# gs_box_board.net
KiCad netlist of a schematic drawn in EAGLE
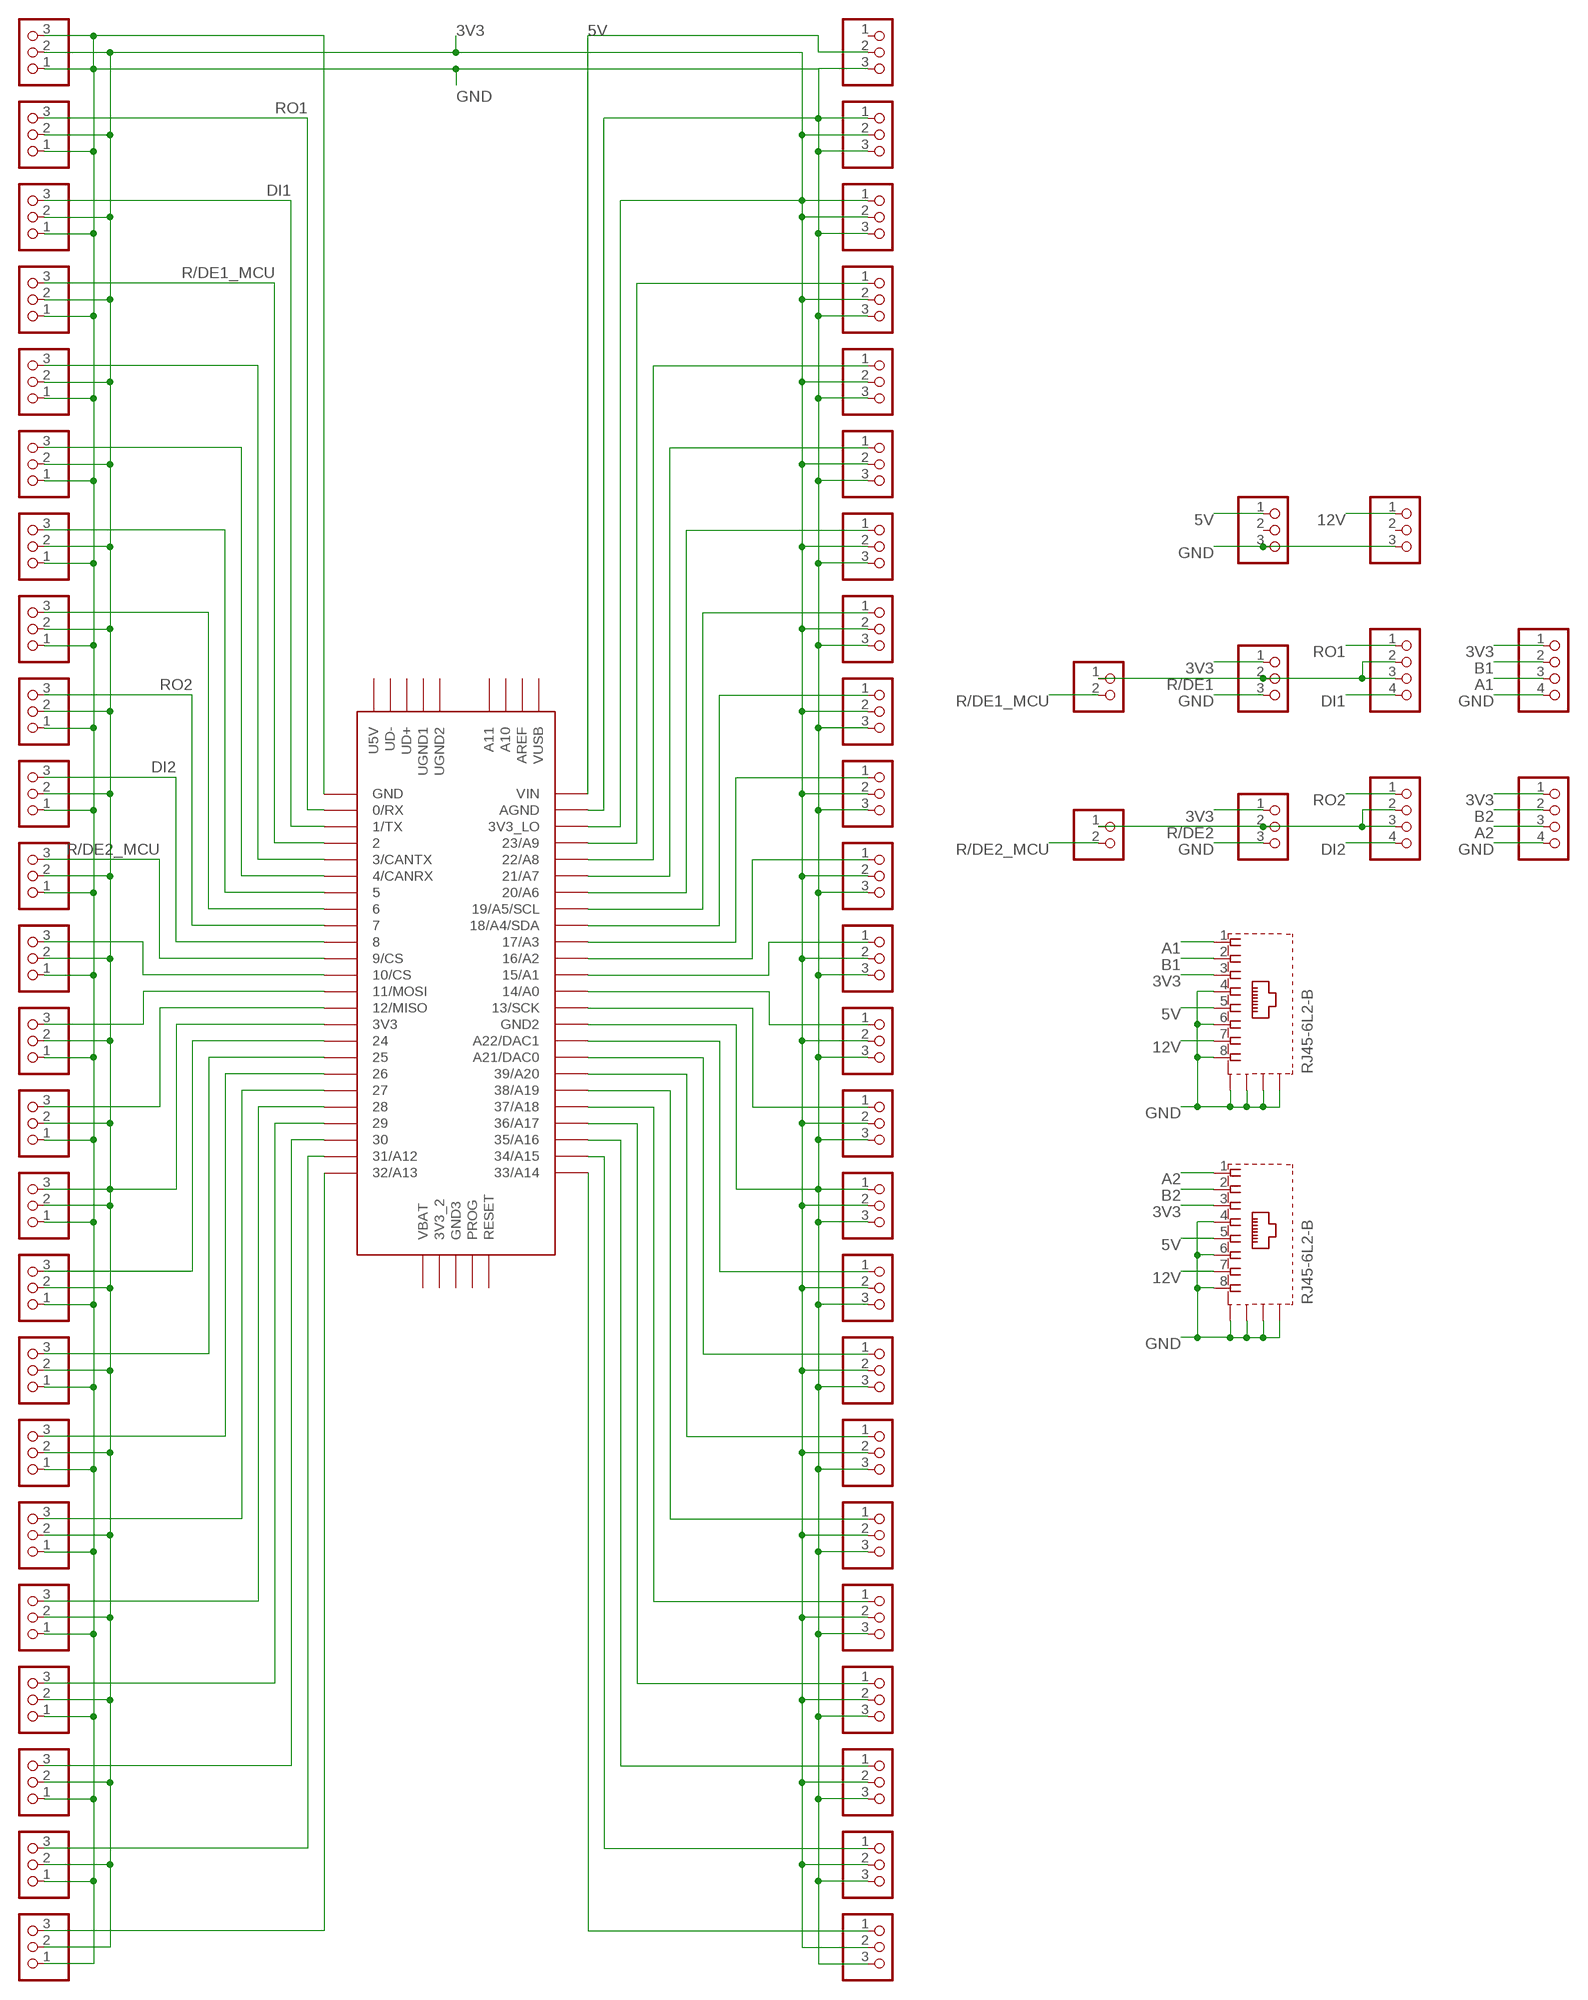
[diagram p0: schematic, sheet 1]

(export (version "E")
  (design (tool "Eeschema 10.0.6"))
  (components
    (comp (ref "JP1")
      (value "PINHD-1X3")
      (footprint "eagle-import:1X03")
      (libsource (lib "eagle-import") (part "PINHD-1X3"))
    )
    (comp (ref "JP2")
      (value "PINHD-1X3")
      (footprint "eagle-import:1X03")
      (libsource (lib "eagle-import") (part "PINHD-1X3"))
    )
    (comp (ref "JP3")
      (value "PINHD-1X3")
      (footprint "eagle-import:1X03")
      (libsource (lib "eagle-import") (part "PINHD-1X3"))
    )
    (comp (ref "JP4")
      (value "PINHD-1X3")
      (footprint "eagle-import:1X03")
      (libsource (lib "eagle-import") (part "PINHD-1X3"))
    )
    (comp (ref "JP5")
      (value "PINHD-1X3")
      (footprint "eagle-import:1X03")
      (libsource (lib "eagle-import") (part "PINHD-1X3"))
    )
    (comp (ref "JP6")
      (value "PINHD-1X3")
      (footprint "eagle-import:1X03")
      (libsource (lib "eagle-import") (part "PINHD-1X3"))
    )
    (comp (ref "JP7")
      (value "PINHD-1X3")
      (footprint "eagle-import:1X03")
      (libsource (lib "eagle-import") (part "PINHD-1X3"))
    )
    (comp (ref "JP8")
      (value "PINHD-1X3")
      (footprint "eagle-import:1X03")
      (libsource (lib "eagle-import") (part "PINHD-1X3"))
    )
    (comp (ref "JP9")
      (value "PINHD-1X3")
      (footprint "eagle-import:1X03")
      (libsource (lib "eagle-import") (part "PINHD-1X3"))
    )
    (comp (ref "JP10")
      (value "PINHD-1X3")
      (footprint "eagle-import:1X03")
      (libsource (lib "eagle-import") (part "PINHD-1X3"))
    )
    (comp (ref "JP11")
      (value "PINHD-1X3")
      (footprint "eagle-import:1X03")
      (libsource (lib "eagle-import") (part "PINHD-1X3"))
    )
    (comp (ref "JP12")
      (value "PINHD-1X3")
      (footprint "eagle-import:1X03")
      (libsource (lib "eagle-import") (part "PINHD-1X3"))
    )
    (comp (ref "JP13")
      (value "PINHD-1X3")
      (footprint "eagle-import:1X03")
      (libsource (lib "eagle-import") (part "PINHD-1X3"))
    )
    (comp (ref "JP14")
      (value "PINHD-1X3")
      (footprint "eagle-import:1X03")
      (libsource (lib "eagle-import") (part "PINHD-1X3"))
    )
    (comp (ref "JP15")
      (value "PINHD-1X3")
      (footprint "eagle-import:1X03")
      (libsource (lib "eagle-import") (part "PINHD-1X3"))
    )
    (comp (ref "JP16")
      (value "PINHD-1X3")
      (footprint "eagle-import:1X03")
      (libsource (lib "eagle-import") (part "PINHD-1X3"))
    )
    (comp (ref "JP17")
      (value "PINHD-1X3")
      (footprint "eagle-import:1X03")
      (libsource (lib "eagle-import") (part "PINHD-1X3"))
    )
    (comp (ref "JP18")
      (value "PINHD-1X3")
      (footprint "eagle-import:1X03")
      (libsource (lib "eagle-import") (part "PINHD-1X3"))
    )
    (comp (ref "JP19")
      (value "PINHD-1X3")
      (footprint "eagle-import:1X03")
      (libsource (lib "eagle-import") (part "PINHD-1X3"))
    )
    (comp (ref "JP20")
      (value "PINHD-1X3")
      (footprint "eagle-import:1X03")
      (libsource (lib "eagle-import") (part "PINHD-1X3"))
    )
    (comp (ref "JP21")
      (value "PINHD-1X3")
      (footprint "eagle-import:1X03")
      (libsource (lib "eagle-import") (part "PINHD-1X3"))
    )
    (comp (ref "JP22")
      (value "PINHD-1X3")
      (footprint "eagle-import:1X03")
      (libsource (lib "eagle-import") (part "PINHD-1X3"))
    )
    (comp (ref "JP23")
      (value "PINHD-1X3")
      (footprint "eagle-import:1X03")
      (libsource (lib "eagle-import") (part "PINHD-1X3"))
    )
    (comp (ref "JP24")
      (value "PINHD-1X3")
      (footprint "eagle-import:1X03")
      (libsource (lib "eagle-import") (part "PINHD-1X3"))
    )
    (comp (ref "JP25")
      (value "PINHD-1X3")
      (footprint "eagle-import:1X03")
      (libsource (lib "eagle-import") (part "PINHD-1X3"))
    )
    (comp (ref "JP26")
      (value "PINHD-1X3")
      (footprint "eagle-import:1X03")
      (libsource (lib "eagle-import") (part "PINHD-1X3"))
    )
    (comp (ref "JP27")
      (value "PINHD-1X3")
      (footprint "eagle-import:1X03")
      (libsource (lib "eagle-import") (part "PINHD-1X3"))
    )
    (comp (ref "JP28")
      (value "PINHD-1X3")
      (footprint "eagle-import:1X03")
      (libsource (lib "eagle-import") (part "PINHD-1X3"))
    )
    (comp (ref "JP29")
      (value "PINHD-1X3")
      (footprint "eagle-import:1X03")
      (libsource (lib "eagle-import") (part "PINHD-1X3"))
    )
    (comp (ref "JP30")
      (value "PINHD-1X3")
      (footprint "eagle-import:1X03")
      (libsource (lib "eagle-import") (part "PINHD-1X3"))
    )
    (comp (ref "JP31")
      (value "PINHD-1X3")
      (footprint "eagle-import:1X03")
      (libsource (lib "eagle-import") (part "PINHD-1X3"))
    )
    (comp (ref "JP32")
      (value "PINHD-1X3")
      (footprint "eagle-import:1X03")
      (libsource (lib "eagle-import") (part "PINHD-1X3"))
    )
    (comp (ref "JP33")
      (value "PINHD-1X3")
      (footprint "eagle-import:1X03")
      (libsource (lib "eagle-import") (part "PINHD-1X3"))
    )
    (comp (ref "JP34")
      (value "PINHD-1X3")
      (footprint "eagle-import:1X03")
      (libsource (lib "eagle-import") (part "PINHD-1X3"))
    )
    (comp (ref "JP35")
      (value "PINHD-1X3")
      (footprint "eagle-import:1X03")
      (libsource (lib "eagle-import") (part "PINHD-1X3"))
    )
    (comp (ref "JP36")
      (value "PINHD-1X3")
      (footprint "eagle-import:1X03")
      (libsource (lib "eagle-import") (part "PINHD-1X3"))
    )
    (comp (ref "JP37")
      (value "PINHD-1X3")
      (footprint "eagle-import:1X03")
      (libsource (lib "eagle-import") (part "PINHD-1X3"))
    )
    (comp (ref "JP38")
      (value "PINHD-1X3")
      (footprint "eagle-import:1X03")
      (libsource (lib "eagle-import") (part "PINHD-1X3"))
    )
    (comp (ref "JP39")
      (value "PINHD-1X3")
      (footprint "eagle-import:1X03")
      (libsource (lib "eagle-import") (part "PINHD-1X3"))
    )
    (comp (ref "JP40")
      (value "PINHD-1X3")
      (footprint "eagle-import:1X03")
      (libsource (lib "eagle-import") (part "PINHD-1X3"))
    )
    (comp (ref "JP41")
      (value "PINHD-1X3")
      (footprint "eagle-import:1X03")
      (libsource (lib "eagle-import") (part "PINHD-1X3"))
    )
    (comp (ref "JP42")
      (value "PINHD-1X3")
      (footprint "eagle-import:1X03")
      (libsource (lib "eagle-import") (part "PINHD-1X3"))
    )
    (comp (ref "JP43")
      (value "PINHD-1X3")
      (footprint "eagle-import:1X03")
      (libsource (lib "eagle-import") (part "PINHD-1X3"))
    )
    (comp (ref "JP44")
      (value "PINHD-1X3")
      (footprint "eagle-import:1X03")
      (libsource (lib "eagle-import") (part "PINHD-1X3"))
    )
    (comp (ref "JP45")
      (value "PINHD-1X3")
      (footprint "eagle-import:1X03")
      (libsource (lib "eagle-import") (part "PINHD-1X3"))
    )
    (comp (ref "JP46")
      (value "PINHD-1X3")
      (footprint "eagle-import:1X03")
      (libsource (lib "eagle-import") (part "PINHD-1X3"))
    )
    (comp (ref "JP47")
      (value "PINHD-1X3")
      (footprint "eagle-import:1X03")
      (libsource (lib "eagle-import") (part "PINHD-1X3"))
    )
    (comp (ref "JP48")
      (value "PINHD-1X3")
      (footprint "eagle-import:1X03")
      (libsource (lib "eagle-import") (part "PINHD-1X3"))
    )
    (comp (ref "JP49")
      (value "PINHD-1X4")
      (footprint "eagle-import:1X04")
      (libsource (lib "eagle-import") (part "PINHD-1X4"))
    )
    (comp (ref "JP50")
      (value "PINHD-1X4")
      (footprint "eagle-import:1X04")
      (libsource (lib "eagle-import") (part "PINHD-1X4"))
    )
    (comp (ref "JP51")
      (value "PINHD-1X4")
      (footprint "eagle-import:1X04")
      (libsource (lib "eagle-import") (part "PINHD-1X4"))
    )
    (comp (ref "JP52")
      (value "PINHD-1X4")
      (footprint "eagle-import:1X04")
      (libsource (lib "eagle-import") (part "PINHD-1X4"))
    )
    (comp (ref "JP53")
      (value "PINHD-1X3")
      (footprint "eagle-import:1X03")
      (libsource (lib "eagle-import") (part "PINHD-1X3"))
    )
    (comp (ref "JP54")
      (value "PINHD-1X3")
      (footprint "eagle-import:1X03")
      (libsource (lib "eagle-import") (part "PINHD-1X3"))
    )
    (comp (ref "JP55")
      (value "PINHD-1X3")
      (footprint "eagle-import:1X03")
      (libsource (lib "eagle-import") (part "PINHD-1X3"))
    )
    (comp (ref "JP56")
      (value "PINHD-1X3")
      (footprint "eagle-import:1X03")
      (libsource (lib "eagle-import") (part "PINHD-1X3"))
    )
    (comp (ref "JP57")
      (value "PINHD-1X2")
      (footprint "eagle-import:1X02")
      (libsource (lib "eagle-import") (part "PINHD-1X2"))
    )
    (comp (ref "JP58")
      (value "PINHD-1X2")
      (footprint "eagle-import:1X02")
      (libsource (lib "eagle-import") (part "PINHD-1X2"))
    )
    (comp (ref "U$1")
      (value "TEENSY_3.5/3.6")
      (footprint "eagle-import:TEENSY_3.5_3.6")
      (libsource (lib "eagle-import") (part "TEENSY_3.5/3.6"))
    )
    (comp (ref "X1")
      (value "RJ45-6L2-B")
      (footprint "eagle-import:RJ45-SHIELD2")
      (libsource (lib "eagle-import") (part "RJ452-B-6L"))
    )
    (comp (ref "X2")
      (value "RJ45-6L2-B")
      (footprint "eagle-import:RJ45-SHIELD2")
      (libsource (lib "eagle-import") (part "RJ452-B-6L"))
    )
  )
  (nets
    (net (code "1") (name "/3V3") (class "Default")
      (node (ref "JP1") (pin "2") (pinfunction "2_2") (pintype "passive"))
      (node (ref "JP10") (pin "2") (pinfunction "2_2") (pintype "passive"))
      (node (ref "JP11") (pin "2") (pinfunction "2_2") (pintype "passive"))
      (node (ref "JP12") (pin "2") (pinfunction "2_2") (pintype "passive"))
      (node (ref "JP13") (pin "2") (pinfunction "2_2") (pintype "passive"))
      (node (ref "JP14") (pin "2") (pinfunction "2_2") (pintype "passive"))
      (node (ref "JP15") (pin "2") (pinfunction "2_2") (pintype "passive"))
      (node (ref "JP16") (pin "2") (pinfunction "2_2") (pintype "passive"))
      (node (ref "JP17") (pin "2") (pinfunction "2_2") (pintype "passive"))
      (node (ref "JP18") (pin "2") (pinfunction "2_2") (pintype "passive"))
      (node (ref "JP19") (pin "2") (pinfunction "2_2") (pintype "passive"))
      (node (ref "JP2") (pin "2") (pinfunction "2_2") (pintype "passive"))
      (node (ref "JP20") (pin "2") (pinfunction "2_2") (pintype "passive"))
      (node (ref "JP22") (pin "2") (pinfunction "2_2") (pintype "passive"))
      (node (ref "JP23") (pin "1") (pinfunction "1_1") (pintype "passive"))
      (node (ref "JP23") (pin "2") (pinfunction "2_2") (pintype "passive"))
      (node (ref "JP24") (pin "2") (pinfunction "2_2") (pintype "passive"))
      (node (ref "JP25") (pin "2") (pinfunction "2_2") (pintype "passive"))
      (node (ref "JP26") (pin "2") (pinfunction "2_2") (pintype "passive"))
      (node (ref "JP27") (pin "2") (pinfunction "2_2") (pintype "passive"))
      (node (ref "JP28") (pin "2") (pinfunction "2_2") (pintype "passive"))
      (node (ref "JP29") (pin "2") (pinfunction "2_2") (pintype "passive"))
      (node (ref "JP3") (pin "2") (pinfunction "2_2") (pintype "passive"))
      (node (ref "JP30") (pin "2") (pinfunction "2_2") (pintype "passive"))
      (node (ref "JP31") (pin "2") (pinfunction "2_2") (pintype "passive"))
      (node (ref "JP32") (pin "2") (pinfunction "2_2") (pintype "passive"))
      (node (ref "JP33") (pin "2") (pinfunction "2_2") (pintype "passive"))
      (node (ref "JP34") (pin "2") (pinfunction "2_2") (pintype "passive"))
      (node (ref "JP35") (pin "2") (pinfunction "2_2") (pintype "passive"))
      (node (ref "JP36") (pin "2") (pinfunction "2_2") (pintype "passive"))
      (node (ref "JP37") (pin "2") (pinfunction "2_2") (pintype "passive"))
      (node (ref "JP38") (pin "2") (pinfunction "2_2") (pintype "passive"))
      (node (ref "JP39") (pin "2") (pinfunction "2_2") (pintype "passive"))
      (node (ref "JP4") (pin "2") (pinfunction "2_2") (pintype "passive"))
      (node (ref "JP40") (pin "2") (pinfunction "2_2") (pintype "passive"))
      (node (ref "JP41") (pin "2") (pinfunction "2_2") (pintype "passive"))
      (node (ref "JP42") (pin "2") (pinfunction "2_2") (pintype "passive"))
      (node (ref "JP43") (pin "2") (pinfunction "2_2") (pintype "passive"))
      (node (ref "JP44") (pin "2") (pinfunction "2_2") (pintype "passive"))
      (node (ref "JP45") (pin "2") (pinfunction "2_2") (pintype "passive"))
      (node (ref "JP46") (pin "2") (pinfunction "2_2") (pintype "passive"))
      (node (ref "JP47") (pin "2") (pinfunction "2_2") (pintype "passive"))
      (node (ref "JP48") (pin "2") (pinfunction "2_2") (pintype "passive"))
      (node (ref "JP5") (pin "2") (pinfunction "2_2") (pintype "passive"))
      (node (ref "JP50") (pin "1") (pinfunction "1_1") (pintype "passive"))
      (node (ref "JP52") (pin "1") (pinfunction "1_1") (pintype "passive"))
      (node (ref "JP53") (pin "1") (pinfunction "1_1") (pintype "passive"))
      (node (ref "JP54") (pin "1") (pinfunction "1_1") (pintype "passive"))
      (node (ref "JP6") (pin "2") (pinfunction "2_2") (pintype "passive"))
      (node (ref "JP6") (pin "3") (pinfunction "3_3") (pintype "passive"))
      (node (ref "JP7") (pin "2") (pinfunction "2_2") (pintype "passive"))
      (node (ref "JP8") (pin "2") (pinfunction "2_2") (pintype "passive"))
      (node (ref "JP9") (pin "2") (pinfunction "2_2") (pintype "passive"))
      (node (ref "U$1") (pin "3V3") (pinfunction "3V3_3V3") (pintype "bidirectional"))
      (node (ref "U$1") (pin "3V3_LO") (pinfunction "3V3_LO_3V3_LO") (pintype "bidirectional"))
      (node (ref "X1") (pin "3") (pinfunction "3_3") (pintype "passive"))
      (node (ref "X2") (pin "3") (pinfunction "3_3") (pintype "passive"))
    )
    (net (code "2") (name "/5V") (class "Default")
      (node (ref "JP21") (pin "2") (pinfunction "2_2") (pintype "passive"))
      (node (ref "JP56") (pin "1") (pinfunction "1_1") (pintype "passive"))
      (node (ref "U$1") (pin "VIN") (pinfunction "VIN_VIN") (pintype "bidirectional"))
      (node (ref "X1") (pin "5") (pinfunction "5_5") (pintype "passive"))
      (node (ref "X2") (pin "5") (pinfunction "5_5") (pintype "passive"))
    )
    (net (code "3") (name "/12V") (class "Default")
      (node (ref "JP55") (pin "1") (pinfunction "1_1") (pintype "passive"))
      (node (ref "X1") (pin "7") (pinfunction "7_7") (pintype "passive"))
      (node (ref "X2") (pin "7") (pinfunction "7_7") (pintype "passive"))
    )
    (net (code "4") (name "/A1") (class "Default")
      (node (ref "JP50") (pin "3") (pinfunction "3_3") (pintype "passive"))
      (node (ref "X1") (pin "1") (pinfunction "1_1") (pintype "passive"))
    )
    (net (code "5") (name "/A2") (class "Default")
      (node (ref "JP52") (pin "3") (pinfunction "3_3") (pintype "passive"))
      (node (ref "X2") (pin "1") (pinfunction "1_1") (pintype "passive"))
    )
    (net (code "6") (name "/B1") (class "Default")
      (node (ref "JP50") (pin "2") (pinfunction "2_2") (pintype "passive"))
      (node (ref "X1") (pin "2") (pinfunction "2_2") (pintype "passive"))
    )
    (net (code "7") (name "/B2") (class "Default")
      (node (ref "JP52") (pin "2") (pinfunction "2_2") (pintype "passive"))
      (node (ref "X2") (pin "2") (pinfunction "2_2") (pintype "passive"))
    )
    (net (code "8") (name "/DI1") (class "Default")
      (node (ref "JP34") (pin "3") (pinfunction "3_3") (pintype "passive"))
      (node (ref "JP49") (pin "4") (pinfunction "4_4") (pintype "passive"))
      (node (ref "U$1") (pin "1/TX") (pinfunction "1/TX_1/TX") (pintype "bidirectional"))
    )
    (net (code "9") (name "/DI2") (class "Default")
      (node (ref "JP41") (pin "3") (pinfunction "3_3") (pintype "passive"))
      (node (ref "JP51") (pin "4") (pinfunction "4_4") (pintype "passive"))
      (node (ref "U$1") (pin "8") (pinfunction "8_8") (pintype "bidirectional"))
    )
    (net (code "10") (name "/GND") (class "Default")
      (node (ref "JP1") (pin "3") (pinfunction "3_3") (pintype "passive"))
      (node (ref "JP10") (pin "1") (pinfunction "1_1") (pintype "passive"))
      (node (ref "JP11") (pin "1") (pinfunction "1_1") (pintype "passive"))
      (node (ref "JP12") (pin "3") (pinfunction "3_3") (pintype "passive"))
      (node (ref "JP13") (pin "3") (pinfunction "3_3") (pintype "passive"))
      (node (ref "JP14") (pin "3") (pinfunction "3_3") (pintype "passive"))
      (node (ref "JP15") (pin "1") (pinfunction "1_1") (pintype "passive"))
      (node (ref "JP15") (pin "3") (pinfunction "3_3") (pintype "passive"))
      (node (ref "JP16") (pin "3") (pinfunction "3_3") (pintype "passive"))
      (node (ref "JP17") (pin "3") (pinfunction "3_3") (pintype "passive"))
      (node (ref "JP18") (pin "3") (pinfunction "3_3") (pintype "passive"))
      (node (ref "JP19") (pin "3") (pinfunction "3_3") (pintype "passive"))
      (node (ref "JP2") (pin "1") (pinfunction "1_1") (pintype "passive"))
      (node (ref "JP20") (pin "3") (pinfunction "3_3") (pintype "passive"))
      (node (ref "JP21") (pin "3") (pinfunction "3_3") (pintype "passive"))
      (node (ref "JP22") (pin "1") (pinfunction "1_1") (pintype "passive"))
      (node (ref "JP22") (pin "3") (pinfunction "3_3") (pintype "passive"))
      (node (ref "JP23") (pin "3") (pinfunction "3_3") (pintype "passive"))
      (node (ref "JP24") (pin "3") (pinfunction "3_3") (pintype "passive"))
      (node (ref "JP25") (pin "3") (pinfunction "3_3") (pintype "passive"))
      (node (ref "JP26") (pin "3") (pinfunction "3_3") (pintype "passive"))
      (node (ref "JP27") (pin "3") (pinfunction "3_3") (pintype "passive"))
      (node (ref "JP28") (pin "3") (pinfunction "3_3") (pintype "passive"))
      (node (ref "JP29") (pin "3") (pinfunction "3_3") (pintype "passive"))
      (node (ref "JP3") (pin "1") (pinfunction "1_1") (pintype "passive"))
      (node (ref "JP30") (pin "3") (pinfunction "3_3") (pintype "passive"))
      (node (ref "JP31") (pin "3") (pinfunction "3_3") (pintype "passive"))
      (node (ref "JP32") (pin "1") (pinfunction "1_1") (pintype "passive"))
      (node (ref "JP32") (pin "3") (pinfunction "3_3") (pintype "passive"))
      (node (ref "JP33") (pin "1") (pinfunction "1_1") (pintype "passive"))
      (node (ref "JP34") (pin "1") (pinfunction "1_1") (pintype "passive"))
      (node (ref "JP35") (pin "1") (pinfunction "1_1") (pintype "passive"))
      (node (ref "JP36") (pin "1") (pinfunction "1_1") (pintype "passive"))
      (node (ref "JP37") (pin "1") (pinfunction "1_1") (pintype "passive"))
      (node (ref "JP38") (pin "1") (pinfunction "1_1") (pintype "passive"))
      (node (ref "JP39") (pin "1") (pinfunction "1_1") (pintype "passive"))
      (node (ref "JP4") (pin "1") (pinfunction "1_1") (pintype "passive"))
      (node (ref "JP40") (pin "1") (pinfunction "1_1") (pintype "passive"))
      (node (ref "JP41") (pin "1") (pinfunction "1_1") (pintype "passive"))
      (node (ref "JP42") (pin "1") (pinfunction "1_1") (pintype "passive"))
      (node (ref "JP43") (pin "1") (pinfunction "1_1") (pintype "passive"))
      (node (ref "JP44") (pin "1") (pinfunction "1_1") (pintype "passive"))
      (node (ref "JP45") (pin "1") (pinfunction "1_1") (pintype "passive"))
      (node (ref "JP46") (pin "3") (pinfunction "3_3") (pintype "passive"))
      (node (ref "JP47") (pin "3") (pinfunction "3_3") (pintype "passive"))
      (node (ref "JP48") (pin "3") (pinfunction "3_3") (pintype "passive"))
      (node (ref "JP5") (pin "1") (pinfunction "1_1") (pintype "passive"))
      (node (ref "JP50") (pin "4") (pinfunction "4_4") (pintype "passive"))
      (node (ref "JP52") (pin "4") (pinfunction "4_4") (pintype "passive"))
      (node (ref "JP53") (pin "3") (pinfunction "3_3") (pintype "passive"))
      (node (ref "JP54") (pin "3") (pinfunction "3_3") (pintype "passive"))
      (node (ref "JP55") (pin "3") (pinfunction "3_3") (pintype "passive"))
      (node (ref "JP56") (pin "3") (pinfunction "3_3") (pintype "passive"))
      (node (ref "JP6") (pin "1") (pinfunction "1_1") (pintype "passive"))
      (node (ref "JP7") (pin "1") (pinfunction "1_1") (pintype "passive"))
      (node (ref "JP8") (pin "1") (pinfunction "1_1") (pintype "passive"))
      (node (ref "JP9") (pin "1") (pinfunction "1_1") (pintype "passive"))
      (node (ref "U$1") (pin "AGND") (pinfunction "AGND_AGND") (pintype "bidirectional"))
      (node (ref "U$1") (pin "GND") (pinfunction "GND_GND") (pintype "bidirectional"))
      (node (ref "U$1") (pin "GND2") (pinfunction "GND2_GND2") (pintype "bidirectional"))
      (node (ref "X1") (pin "4") (pinfunction "4_4") (pintype "passive"))
      (node (ref "X1") (pin "6") (pinfunction "6_6") (pintype "passive"))
      (node (ref "X1") (pin "8") (pinfunction "8_8") (pintype "passive"))
      (node (ref "X1") (pin "S1") (pinfunction "S_S1") (pintype "passive"))
      (node (ref "X1") (pin "S2") (pinfunction "S_S2") (pintype "passive"))
      (node (ref "X1") (pin "S3") (pinfunction "S_S3") (pintype "passive"))
      (node (ref "X1") (pin "S4") (pinfunction "S_S4") (pintype "passive"))
      (node (ref "X2") (pin "4") (pinfunction "4_4") (pintype "passive"))
      (node (ref "X2") (pin "6") (pinfunction "6_6") (pintype "passive"))
      (node (ref "X2") (pin "8") (pinfunction "8_8") (pintype "passive"))
      (node (ref "X2") (pin "S1") (pinfunction "S_S1") (pintype "passive"))
      (node (ref "X2") (pin "S2") (pinfunction "S_S2") (pintype "passive"))
      (node (ref "X2") (pin "S3") (pinfunction "S_S3") (pintype "passive"))
      (node (ref "X2") (pin "S4") (pinfunction "S_S4") (pintype "passive"))
    )
    (net (code "11") (name "/RO1") (class "Default")
      (node (ref "JP33") (pin "3") (pinfunction "3_3") (pintype "passive"))
      (node (ref "JP49") (pin "1") (pinfunction "1_1") (pintype "passive"))
      (node (ref "U$1") (pin "0/RX") (pinfunction "0/RX_0/RX") (pintype "bidirectional"))
    )
    (net (code "12") (name "/RO2") (class "Default")
      (node (ref "JP40") (pin "3") (pinfunction "3_3") (pintype "passive"))
      (node (ref "JP51") (pin "1") (pinfunction "1_1") (pintype "passive"))
      (node (ref "U$1") (pin "7") (pinfunction "7_7") (pintype "bidirectional"))
    )
    (net (code "13") (name "/R{slash}DE1") (class "Default")
      (node (ref "JP49") (pin "2") (pinfunction "2_2") (pintype "passive"))
      (node (ref "JP49") (pin "3") (pinfunction "3_3") (pintype "passive"))
      (node (ref "JP53") (pin "2") (pinfunction "2_2") (pintype "passive"))
      (node (ref "JP58") (pin "1") (pinfunction "1_1") (pintype "passive"))
    )
    (net (code "14") (name "/R{slash}DE1_MCU") (class "Default")
      (node (ref "JP35") (pin "3") (pinfunction "3_3") (pintype "passive"))
      (node (ref "JP58") (pin "2") (pinfunction "2_2") (pintype "passive"))
      (node (ref "U$1") (pin "2") (pinfunction "2_2") (pintype "bidirectional"))
    )
    (net (code "15") (name "/R{slash}DE2") (class "Default")
      (node (ref "JP51") (pin "2") (pinfunction "2_2") (pintype "passive"))
      (node (ref "JP51") (pin "3") (pinfunction "3_3") (pintype "passive"))
      (node (ref "JP54") (pin "2") (pinfunction "2_2") (pintype "passive"))
      (node (ref "JP57") (pin "1") (pinfunction "1_1") (pintype "passive"))
    )
    (net (code "16") (name "/R{slash}DE2_MCU") (class "Default")
      (node (ref "JP2") (pin "3") (pinfunction "3_3") (pintype "passive"))
      (node (ref "JP57") (pin "2") (pinfunction "2_2") (pintype "passive"))
      (node (ref "U$1") (pin "9/CS") (pinfunction "9/CS_9/CS") (pintype "bidirectional"))
    )
    (net (code "17") (name "Net-(JP1-Pad1)") (class "Default")
      (node (ref "JP1") (pin "1") (pinfunction "1_1") (pintype "passive"))
      (node (ref "U$1") (pin "16/A2") (pinfunction "16/A2_16/A2") (pintype "bidirectional"))
    )
    (net (code "18") (name "Net-(JP3-Pad3)") (class "Default")
      (node (ref "JP3") (pin "3") (pinfunction "3_3") (pintype "passive"))
      (node (ref "U$1") (pin "10/CS") (pinfunction "10/CS_10/CS") (pintype "bidirectional"))
    )
    (net (code "19") (name "Net-(JP4-Pad3)") (class "Default")
      (node (ref "JP4") (pin "3") (pinfunction "3_3") (pintype "passive"))
      (node (ref "U$1") (pin "11/MOSI") (pinfunction "11/MOSI_11/MOSI") (pintype "bidirectional"))
    )
    (net (code "20") (name "Net-(JP5-Pad3)") (class "Default")
      (node (ref "JP5") (pin "3") (pinfunction "3_3") (pintype "passive"))
      (node (ref "U$1") (pin "12/MISO") (pinfunction "12/MISO_12/MISO") (pintype "bidirectional"))
    )
    (net (code "21") (name "Net-(JP7-Pad3)") (class "Default")
      (node (ref "JP7") (pin "3") (pinfunction "3_3") (pintype "passive"))
      (node (ref "U$1") (pin "24") (pinfunction "24_24") (pintype "bidirectional"))
    )
    (net (code "22") (name "Net-(JP8-Pad3)") (class "Default")
      (node (ref "JP8") (pin "3") (pinfunction "3_3") (pintype "passive"))
      (node (ref "U$1") (pin "25") (pinfunction "25_25") (pintype "bidirectional"))
    )
    (net (code "23") (name "Net-(JP9-Pad3)") (class "Default")
      (node (ref "JP9") (pin "3") (pinfunction "3_3") (pintype "passive"))
      (node (ref "U$1") (pin "26") (pinfunction "26_26") (pintype "bidirectional"))
    )
    (net (code "24") (name "Net-(JP10-Pad3)") (class "Default")
      (node (ref "JP10") (pin "3") (pinfunction "3_3") (pintype "passive"))
      (node (ref "U$1") (pin "27") (pinfunction "27_27") (pintype "bidirectional"))
    )
    (net (code "25") (name "Net-(JP11-Pad3)") (class "Default")
      (node (ref "JP11") (pin "3") (pinfunction "3_3") (pintype "passive"))
      (node (ref "U$1") (pin "28") (pinfunction "28_28") (pintype "bidirectional"))
    )
    (net (code "26") (name "Net-(JP12-Pad1)") (class "Default")
      (node (ref "JP12") (pin "1") (pinfunction "1_1") (pintype "passive"))
      (node (ref "U$1") (pin "15/A1") (pinfunction "15/A1_15/A1") (pintype "bidirectional"))
    )
    (net (code "27") (name "Net-(JP13-Pad1)") (class "Default")
      (node (ref "JP13") (pin "1") (pinfunction "1_1") (pintype "passive"))
      (node (ref "U$1") (pin "14/A0") (pinfunction "14/A0_14/A0") (pintype "bidirectional"))
    )
    (net (code "28") (name "Net-(JP14-Pad1)") (class "Default")
      (node (ref "JP14") (pin "1") (pinfunction "1_1") (pintype "passive"))
      (node (ref "U$1") (pin "13/SCK") (pinfunction "13/SCK_13/SCK") (pintype "bidirectional"))
    )
    (net (code "29") (name "Net-(JP16-Pad1)") (class "Default")
      (node (ref "JP16") (pin "1") (pinfunction "1_1") (pintype "passive"))
      (node (ref "U$1") (pin "A22/DAC1") (pinfunction "A22/DAC1_A22/DAC1") (pintype "bidirectional"))
    )
    (net (code "30") (name "Net-(JP18-Pad1)") (class "Default")
      (node (ref "JP18") (pin "1") (pinfunction "1_1") (pintype "passive"))
      (node (ref "U$1") (pin "39/A20") (pinfunction "39/A20_39/A20") (pintype "bidirectional"))
    )
    (net (code "31") (name "Net-(JP19-Pad1)") (class "Default")
      (node (ref "JP19") (pin "1") (pinfunction "1_1") (pintype "passive"))
      (node (ref "U$1") (pin "38/A19") (pinfunction "38/A19_38/A19") (pintype "bidirectional"))
    )
    (net (code "32") (name "Net-(JP20-Pad1)") (class "Default")
      (node (ref "JP20") (pin "1") (pinfunction "1_1") (pintype "passive"))
      (node (ref "U$1") (pin "37/A18") (pinfunction "37/A18_37/A18") (pintype "bidirectional"))
    )
    (net (code "33") (name "Net-(JP24-Pad1)") (class "Default")
      (node (ref "JP24") (pin "1") (pinfunction "1_1") (pintype "passive"))
      (node (ref "U$1") (pin "23/A9") (pinfunction "23/A9_23/A9") (pintype "bidirectional"))
    )
    (net (code "34") (name "Net-(JP25-Pad1)") (class "Default")
      (node (ref "JP25") (pin "1") (pinfunction "1_1") (pintype "passive"))
      (node (ref "U$1") (pin "22/A8") (pinfunction "22/A8_22/A8") (pintype "bidirectional"))
    )
    (net (code "35") (name "Net-(JP26-Pad1)") (class "Default")
      (node (ref "JP26") (pin "1") (pinfunction "1_1") (pintype "passive"))
      (node (ref "U$1") (pin "21/A7") (pinfunction "21/A7_21/A7") (pintype "bidirectional"))
    )
    (net (code "36") (name "Net-(JP27-Pad1)") (class "Default")
      (node (ref "JP27") (pin "1") (pinfunction "1_1") (pintype "passive"))
      (node (ref "U$1") (pin "20/A6") (pinfunction "20/A6_20/A6") (pintype "bidirectional"))
    )
    (net (code "37") (name "Net-(JP28-Pad1)") (class "Default")
      (node (ref "JP28") (pin "1") (pinfunction "1_1") (pintype "passive"))
      (node (ref "U$1") (pin "19/A5/SCL") (pinfunction "19/A5/SCL_19/A5/SCL") (pintype "bidirectional"))
    )
    (net (code "38") (name "Net-(JP29-Pad1)") (class "Default")
      (node (ref "JP29") (pin "1") (pinfunction "1_1") (pintype "passive"))
      (node (ref "U$1") (pin "18/A4/SDA") (pinfunction "18/A4/SDA_18/A4/SDA") (pintype "bidirectional"))
    )
    (net (code "39") (name "Net-(JP30-Pad1)") (class "Default")
      (node (ref "JP30") (pin "1") (pinfunction "1_1") (pintype "passive"))
      (node (ref "U$1") (pin "17/A3") (pinfunction "17/A3_17/A3") (pintype "bidirectional"))
    )
    (net (code "40") (name "Net-(JP31-Pad1)") (class "Default")
      (node (ref "JP31") (pin "1") (pinfunction "1_1") (pintype "passive"))
      (node (ref "U$1") (pin "36/A17") (pinfunction "36/A17_36/A17") (pintype "bidirectional"))
    )
    (net (code "41") (name "Net-(JP36-Pad3)") (class "Default")
      (node (ref "JP36") (pin "3") (pinfunction "3_3") (pintype "passive"))
      (node (ref "U$1") (pin "3/CANTX") (pinfunction "3/CANTX_3/CANTX") (pintype "bidirectional"))
    )
    (net (code "42") (name "Net-(JP37-Pad3)") (class "Default")
      (node (ref "JP37") (pin "3") (pinfunction "3_3") (pintype "passive"))
      (node (ref "U$1") (pin "4/CANRX") (pinfunction "4/CANRX_4/CANRX") (pintype "bidirectional"))
    )
    (net (code "43") (name "Net-(JP38-Pad3)") (class "Default")
      (node (ref "JP38") (pin "3") (pinfunction "3_3") (pintype "passive"))
      (node (ref "U$1") (pin "5") (pinfunction "5_5") (pintype "bidirectional"))
    )
    (net (code "44") (name "Net-(JP39-Pad3)") (class "Default")
      (node (ref "JP39") (pin "3") (pinfunction "3_3") (pintype "passive"))
      (node (ref "U$1") (pin "6") (pinfunction "6_6") (pintype "bidirectional"))
    )
    (net (code "45") (name "Net-(JP42-Pad3)") (class "Default")
      (node (ref "JP42") (pin "3") (pinfunction "3_3") (pintype "passive"))
      (node (ref "U$1") (pin "29") (pinfunction "29_29") (pintype "bidirectional"))
    )
    (net (code "46") (name "Net-(JP43-Pad3)") (class "Default")
      (node (ref "JP43") (pin "3") (pinfunction "3_3") (pintype "passive"))
      (node (ref "U$1") (pin "30") (pinfunction "30_30") (pintype "bidirectional"))
    )
    (net (code "47") (name "Net-(JP44-Pad3)") (class "Default")
      (node (ref "JP44") (pin "3") (pinfunction "3_3") (pintype "passive"))
      (node (ref "U$1") (pin "31/A12") (pinfunction "31/A12_31/A12") (pintype "bidirectional"))
    )
    (net (code "48") (name "Net-(JP45-Pad3)") (class "Default")
      (node (ref "JP45") (pin "3") (pinfunction "3_3") (pintype "passive"))
      (node (ref "U$1") (pin "32/A13") (pinfunction "32/A13_32/A13") (pintype "bidirectional"))
    )
    (net (code "49") (name "Net-(JP46-Pad1)") (class "Default")
      (node (ref "JP46") (pin "1") (pinfunction "1_1") (pintype "passive"))
      (node (ref "U$1") (pin "35/A16") (pinfunction "35/A16_35/A16") (pintype "bidirectional"))
    )
    (net (code "50") (name "Net-(JP47-Pad1)") (class "Default")
      (node (ref "JP47") (pin "1") (pinfunction "1_1") (pintype "passive"))
      (node (ref "U$1") (pin "34/A15") (pinfunction "34/A15_34/A15") (pintype "bidirectional"))
    )
    (net (code "51") (name "Net-(JP48-Pad1)") (class "Default")
      (node (ref "JP48") (pin "1") (pinfunction "1_1") (pintype "passive"))
      (node (ref "U$1") (pin "33/A14") (pinfunction "33/A14_33/A14") (pintype "bidirectional"))
    )
    (net (code "52") (name "Net-(U$1-A21{slash}DAC0)") (class "Default")
      (node (ref "JP17") (pin "1") (pinfunction "1_1") (pintype "passive"))
      (node (ref "U$1") (pin "21/DAC0") (pinfunction "A21/DAC0_21/DAC0") (pintype "bidirectional"))
    )
    (net (code "53") (name "unconnected-(JP21-Pad1)") (class "Default")
      (node (ref "JP21") (pin "1") (pinfunction "1_1") (pintype "passive"))
    )
    (net (code "54") (name "unconnected-(JP55-Pad2)") (class "Default")
      (node (ref "JP55") (pin "2") (pinfunction "2_2") (pintype "passive"))
    )
    (net (code "55") (name "unconnected-(JP56-Pad2)") (class "Default")
      (node (ref "JP56") (pin "2") (pinfunction "2_2") (pintype "passive"))
    )
    (net (code "56") (name "unconnected-(U$1-Pad3V3_2)") (class "Default")
      (node (ref "U$1") (pin "3V3_2") (pinfunction "3V3_2_3V3_2") (pintype "bidirectional"))
    )
    (net (code "57") (name "unconnected-(U$1-PadA10)") (class "Default")
      (node (ref "U$1") (pin "A10") (pinfunction "A10_A10") (pintype "bidirectional"))
    )
    (net (code "58") (name "unconnected-(U$1-PadA11)") (class "Default")
      (node (ref "U$1") (pin "A11") (pinfunction "A11_A11") (pintype "bidirectional"))
    )
    (net (code "59") (name "unconnected-(U$1-PadAREF)") (class "Default")
      (node (ref "U$1") (pin "AREF") (pinfunction "AREF_AREF") (pintype "bidirectional"))
    )
    (net (code "60") (name "unconnected-(U$1-PadGND3)") (class "Default")
      (node (ref "U$1") (pin "GND3") (pinfunction "GND3_GND3") (pintype "bidirectional"))
    )
    (net (code "61") (name "unconnected-(U$1-PadPROG)") (class "Default")
      (node (ref "U$1") (pin "PROG") (pinfunction "PROG_PROG") (pintype "bidirectional"))
    )
    (net (code "62") (name "unconnected-(U$1-PadRESET)") (class "Default")
      (node (ref "U$1") (pin "RESET") (pinfunction "RESET_RESET") (pintype "bidirectional"))
    )
    (net (code "63") (name "unconnected-(U$1-PadU5V)") (class "Default")
      (node (ref "U$1") (pin "U5V") (pinfunction "U5V_U5V") (pintype "bidirectional"))
    )
    (net (code "64") (name "unconnected-(U$1-PadUD+)") (class "Default")
      (node (ref "U$1") (pin "UD+") (pinfunction "UD+_UD+") (pintype "bidirectional"))
    )
    (net (code "65") (name "unconnected-(U$1-PadUD-)") (class "Default")
      (node (ref "U$1") (pin "UD-") (pinfunction "UD-_UD-") (pintype "bidirectional"))
    )
    (net (code "66") (name "unconnected-(U$1-PadUGND1)") (class "Default")
      (node (ref "U$1") (pin "UGND1") (pinfunction "UGND1_UGND1") (pintype "bidirectional"))
    )
    (net (code "67") (name "unconnected-(U$1-PadUGND2)") (class "Default")
      (node (ref "U$1") (pin "UGND2") (pinfunction "UGND2_UGND2") (pintype "bidirectional"))
    )
    (net (code "68") (name "unconnected-(U$1-PadVBAT)") (class "Default")
      (node (ref "U$1") (pin "VBAT") (pinfunction "VBAT_VBAT") (pintype "bidirectional"))
    )
    (net (code "69") (name "unconnected-(U$1-PadVUSB)") (class "Default")
      (node (ref "U$1") (pin "VUSB") (pinfunction "VUSB_VUSB") (pintype "bidirectional"))
    )
  )
)
